# IOX_77_easyEDA_proj_2026-04-07.net
KiCad netlist of a schematic drawn in EasyEDA Pro
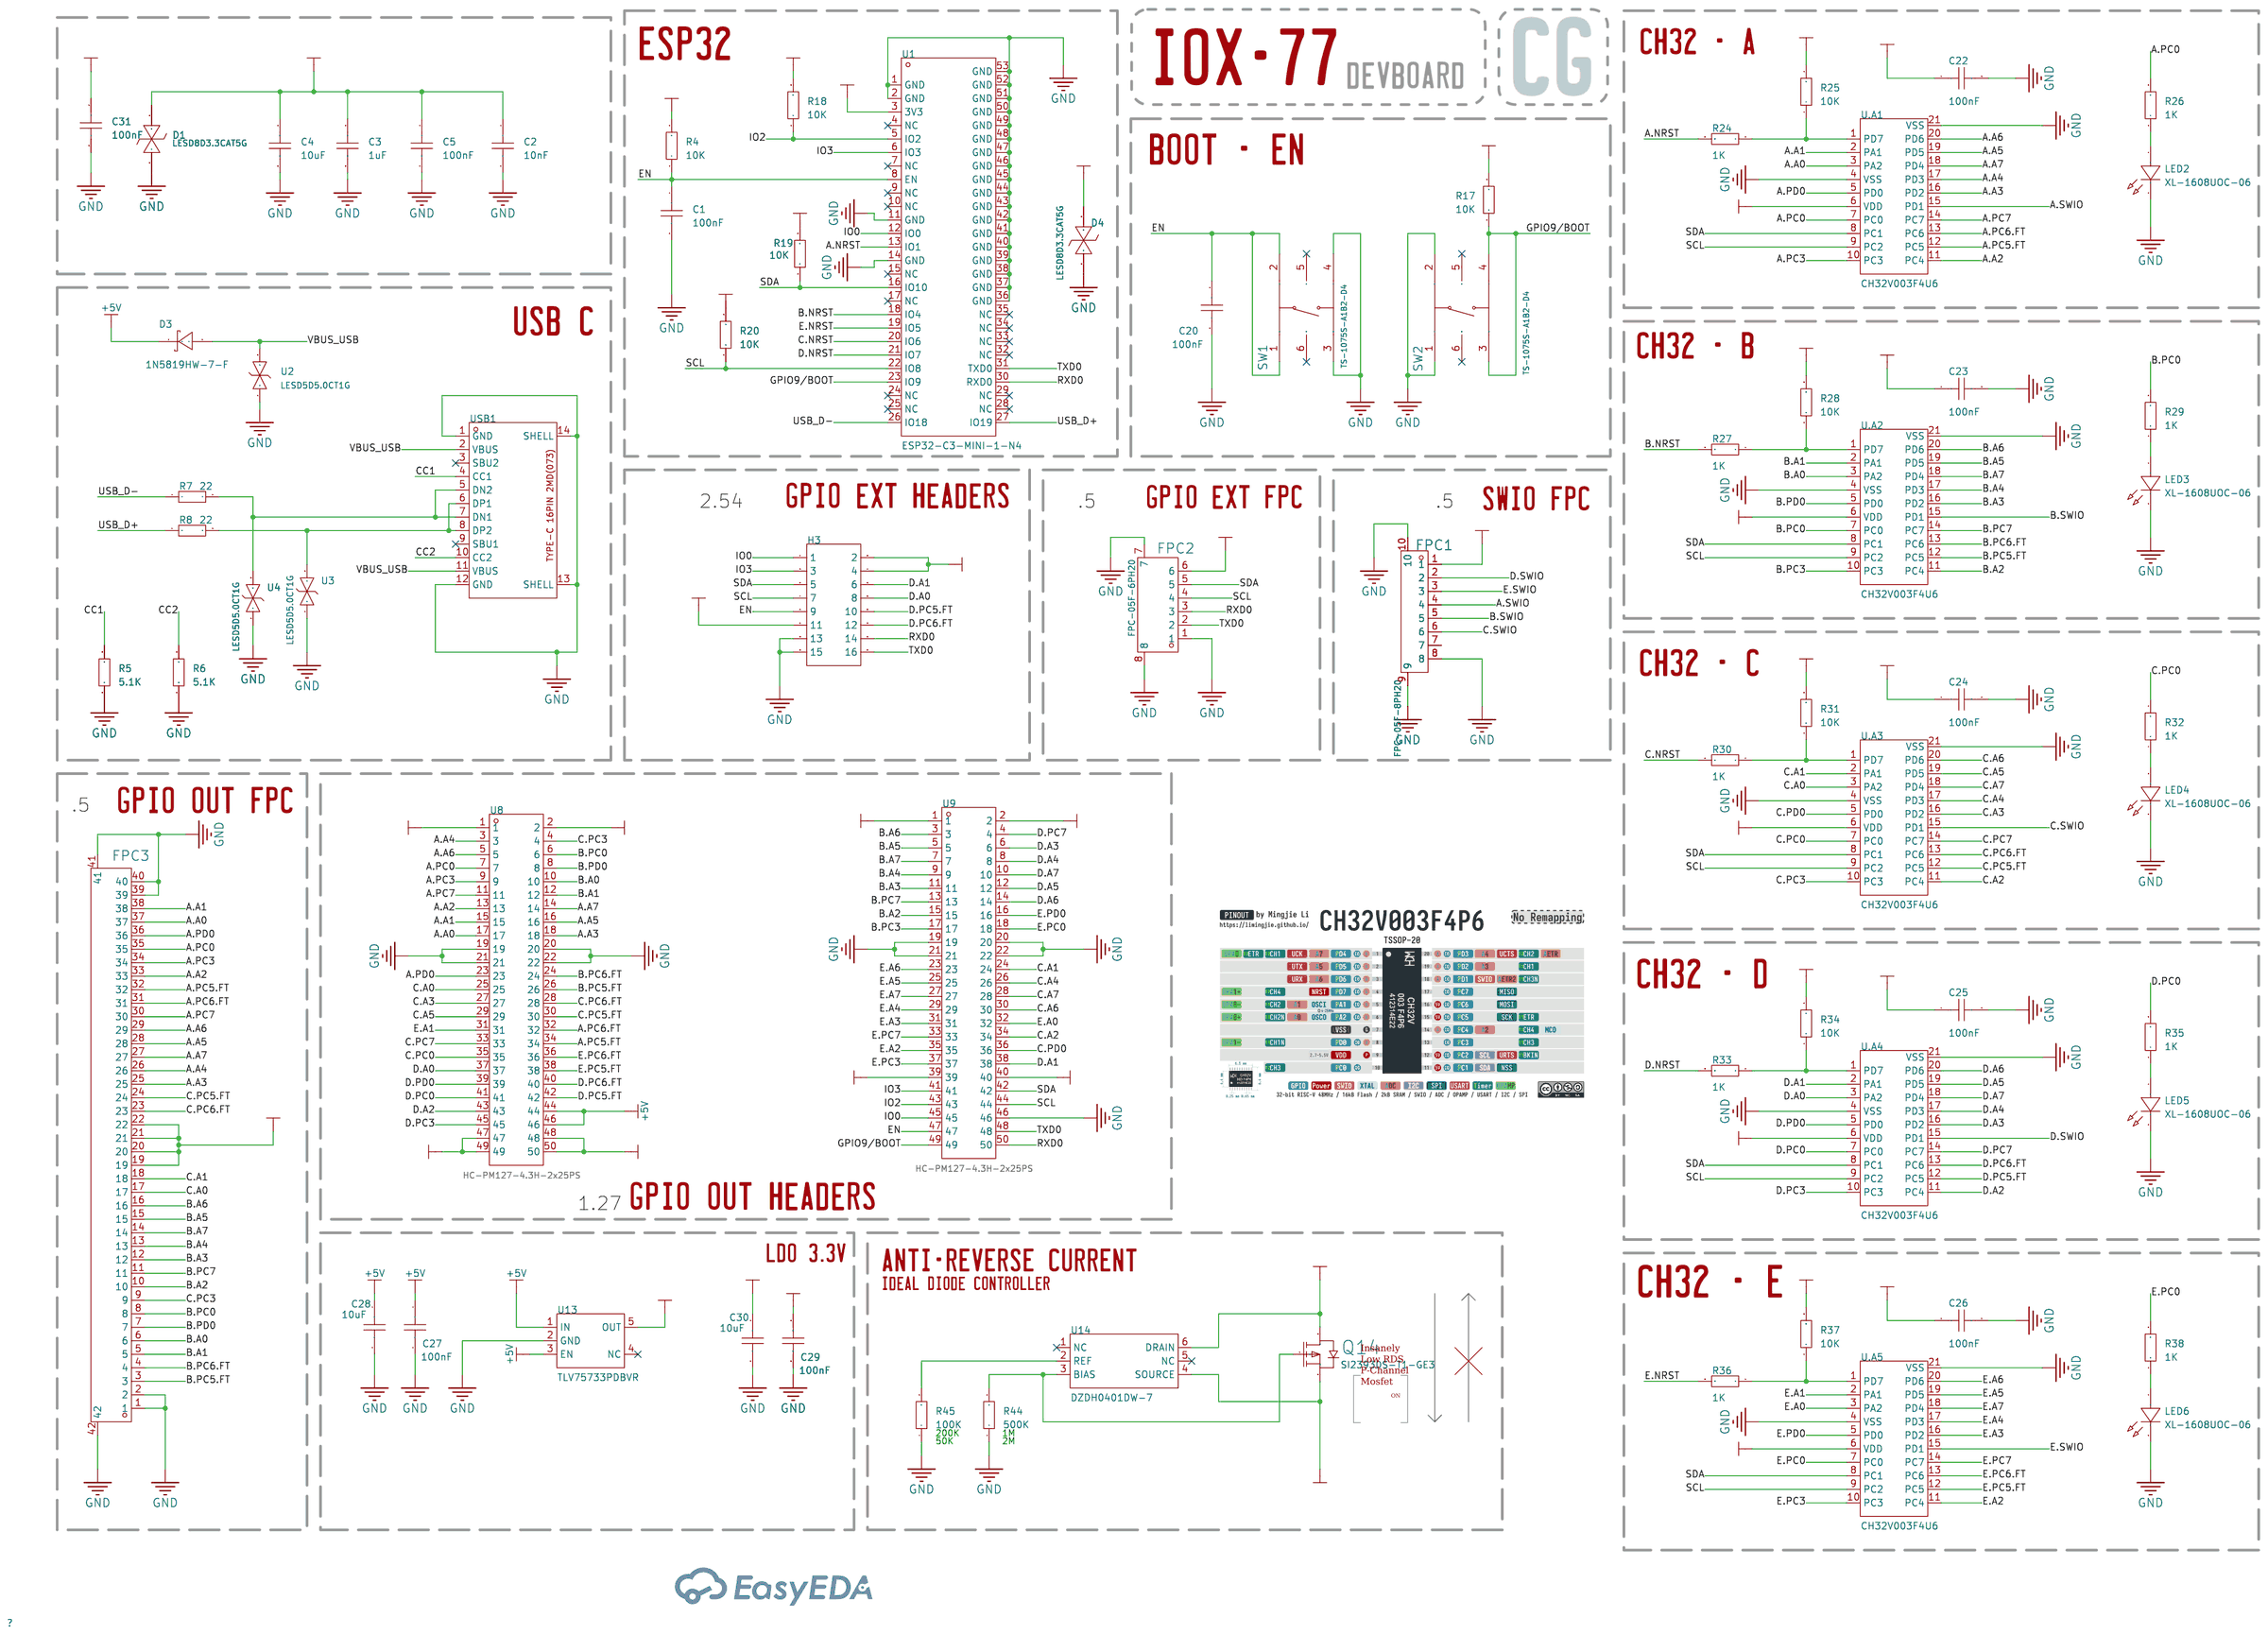
[diagram p0: schematic sheet]

(export (version "E")
  (design (tool "Eeschema 10.0.6"))
  (components
    (comp (ref "C1")
      (value "100nF")
      (footprint "easyedapro:C0603")
      (libsource (lib "easyedapro") (part "CAP"))
    )
    (comp (ref "C2")
      (value "10nF")
      (footprint "easyedapro:C0603")
      (description "Capacitance:10nF Tolerance:±10% Tolerance:±10% Voltage Rating:16V Temperature Coefficient:X7R")
      (fields
        (field (name "Manufacturer Part") "CC0603KRX7R7BB103")
        (field (name "Manufacturer") "YAGEO(国巨)")
      )
      (libsource (lib "easyedapro") (part "CAP"))
    )
    (comp (ref "C3")
      (value "1uF")
      (footprint "easyedapro:C0603")
      (description "Capacitance:1uF Tolerance:±10% Tolerance:±10% Voltage Rating:16V Temperature Coefficient:X5R")
      (fields
        (field (name "Manufacturer Part") "CL10A105KO8NNNC")
        (field (name "Manufacturer") "SAMSUNG(三星)")
      )
      (libsource (lib "easyedapro") (part "CAP"))
    )
    (comp (ref "C4")
      (value "10uF")
      (footprint "easyedapro:C0603")
      (description "Capacitance:10uF Tolerance:±10% Tolerance:±10% Voltage Rating:16V Temperature Coefficient:X5R")
      (fields
        (field (name "Manufacturer Part") "CL21A106KOQNNNE")
        (field (name "Manufacturer") "SAMSUNG(三星)")
      )
      (libsource (lib "easyedapro") (part "CAP"))
    )
    (comp (ref "C5")
      (value "100nF")
      (footprint "easyedapro:C0603")
      (description "Capacitance:100nF Tolerance:±10% Tolerance:±10% Voltage Rating:16V Temperature Coefficient:X7R")
      (fields
        (field (name "Manufacturer Part") "CL10B104KO8NNNC")
        (field (name "Manufacturer") "SAMSUNG(三星)")
      )
      (libsource (lib "easyedapro") (part "CAP"))
    )
    (comp (ref "C20")
      (value "100nF")
      (footprint "easyedapro:C0603")
      (description "Capacitance:100nF Tolerance:±10% Tolerance:±10% Voltage Rating:16V Temperature Coefficient:X7R")
      (fields
        (field (name "Manufacturer Part") "CL10B104KO8NNNC")
        (field (name "Manufacturer") "SAMSUNG(三星)")
      )
      (libsource (lib "easyedapro") (part "CAP"))
    )
    (comp (ref "C22")
      (value "100nF")
      (footprint "easyedapro:C0603")
      (description "Capacitance:100nF Tolerance:±10% Tolerance:±10% Voltage Rating:16V Temperature Coefficient:X7R")
      (fields
        (field (name "Manufacturer Part") "CL10B104KO8NNNC")
        (field (name "Manufacturer") "SAMSUNG(三星)")
      )
      (libsource (lib "easyedapro") (part "CAP"))
    )
    (comp (ref "C23")
      (value "100nF")
      (footprint "easyedapro:C0603")
      (description "Capacitance:100nF Tolerance:±10% Tolerance:±10% Voltage Rating:16V Temperature Coefficient:X7R")
      (fields
        (field (name "Manufacturer Part") "CL10B104KO8NNNC")
        (field (name "Manufacturer") "SAMSUNG(三星)")
      )
      (libsource (lib "easyedapro") (part "CAP"))
    )
    (comp (ref "C24")
      (value "100nF")
      (footprint "easyedapro:C0603")
      (description "Capacitance:100nF Tolerance:±10% Tolerance:±10% Voltage Rating:16V Temperature Coefficient:X7R")
      (fields
        (field (name "Manufacturer Part") "CL10B104KO8NNNC")
        (field (name "Manufacturer") "SAMSUNG(三星)")
      )
      (libsource (lib "easyedapro") (part "CAP"))
    )
    (comp (ref "C25")
      (value "100nF")
      (footprint "easyedapro:C0603")
      (description "Capacitance:100nF Tolerance:±10% Tolerance:±10% Voltage Rating:16V Temperature Coefficient:X7R")
      (fields
        (field (name "Manufacturer Part") "CL10B104KO8NNNC")
        (field (name "Manufacturer") "SAMSUNG(三星)")
      )
      (libsource (lib "easyedapro") (part "CAP"))
    )
    (comp (ref "C26")
      (value "100nF")
      (footprint "easyedapro:C0603")
      (description "Capacitance:100nF Tolerance:±10% Tolerance:±10% Voltage Rating:16V Temperature Coefficient:X7R")
      (fields
        (field (name "Manufacturer Part") "CL10B104KO8NNNC")
        (field (name "Manufacturer") "SAMSUNG(三星)")
      )
      (libsource (lib "easyedapro") (part "CAP"))
    )
    (comp (ref "C27")
      (value "100nF")
      (footprint "easyedapro:C0603")
      (description "Capacitance:100nF Tolerance:±10% Tolerance:±10% Voltage Rating:16V Temperature Coefficient:X7R")
      (fields
        (field (name "Manufacturer Part") "CL10B104KO8NNNC")
        (field (name "Manufacturer") "SAMSUNG(三星)")
      )
      (libsource (lib "easyedapro") (part "CAP"))
    )
    (comp (ref "C28")
      (value "10uF")
      (footprint "easyedapro:C0603")
      (description "Capacitance:10uF Tolerance:±10% Tolerance:±10% Voltage Rating:16V Temperature Coefficient:X5R")
      (fields
        (field (name "Manufacturer Part") "CL21A106KOQNNNE")
        (field (name "Manufacturer") "SAMSUNG(三星)")
      )
      (libsource (lib "easyedapro") (part "CAP"))
    )
    (comp (ref "C29")
      (value "100nF")
      (footprint "easyedapro:C0603")
      (description "Capacitance:100nF Tolerance:±10% Tolerance:±10% Voltage Rating:16V Temperature Coefficient:X7R")
      (fields
        (field (name "Manufacturer Part") "CL10B104KO8NNNC")
        (field (name "Manufacturer") "SAMSUNG(三星)")
      )
      (libsource (lib "easyedapro") (part "CAP"))
    )
    (comp (ref "C30")
      (value "10uF")
      (footprint "easyedapro:C0603")
      (description "Capacitance:10uF Tolerance:±10% Tolerance:±10% Voltage Rating:16V Temperature Coefficient:X5R")
      (fields
        (field (name "Manufacturer Part") "CL21A106KOQNNNE")
        (field (name "Manufacturer") "SAMSUNG(三星)")
      )
      (libsource (lib "easyedapro") (part "CAP"))
    )
    (comp (ref "C31")
      (value "100nF")
      (footprint "easyedapro:C0603")
      (description "Capacitance:10nF Tolerance:±10% Tolerance:±10% Voltage Rating:16V Temperature Coefficient:X7R")
      (fields
        (field (name "Manufacturer Part") "CC0603KRX7R7BB103")
        (field (name "Manufacturer") "YAGEO(国巨)")
      )
      (libsource (lib "easyedapro") (part "CAP"))
    )
    (comp (ref "D1")
      (value "LESD8D3.3CAT5G")
      (footprint "easyedapro:SOD-882_L1.0-W0.6-BI")
      (fields (field (name "Manufacturer") "FUXINSEMI(富芯森美)"))
      (libsource (lib "easyedapro") (part "LESD8D3.3CAT5G_C5563754"))
    )
    (comp (ref "D3")
      (value "1N5819HW-7-F")
      (footprint "easyedapro:SOD-123_L2.7-W1.6-LS3.7-RD")
      (fields (field (name "Manufacturer") "DIODES(美台)"))
      (libsource (lib "easyedapro") (part "1N5819HW-7-F"))
    )
    (comp (ref "D4")
      (value "LESD8D3.3CAT5G")
      (footprint "easyedapro:SOD-882_L1.0-W0.6-BI")
      (fields (field (name "Manufacturer") "FUXINSEMI(富芯森美)"))
      (libsource (lib "easyedapro") (part "LESD8D3.3CAT5G_C5563754"))
    )
    (comp (ref "FPC1")
      (value "FPC-05F-8PH20")
      (footprint "easyedapro:FPC-SMD_8P-P0.50_FPC-05F-8PH20")
      (fields (field (name "Manufacturer") "XUNPU(讯普)"))
      (libsource (lib "easyedapro") (part "FPC-05F-8PH20"))
    )
    (comp (ref "FPC2")
      (value "FPC-05F-6PH20")
      (footprint "easyedapro:FPC-SMD_6P-P0.50_XUNPU_FPC-05F-6PH20")
      (fields (field (name "Manufacturer") "XUNPU(讯普)"))
      (libsource (lib "easyedapro") (part "FPC-05F-6PH20"))
    )
    (comp (ref "FPC3")
      (value "FPC-05F-40PH20")
      (footprint "easyedapro:FPC-SMD_40P-P0.50_FPC-05F-40PH20")
      (fields (field (name "Manufacturer") "XUNPU(讯普)"))
      (libsource (lib "easyedapro") (part "FPC-05F-40PH20"))
    )
    (comp (ref "H3")
      (value "~")
      (footprint "easyedapro:HDR-TH_16P-P2.54-V-M-R2-C8-S2.54")
      (libsource (lib "easyedapro") (part "HDR-M-2.54_2x8"))
    )
    (comp (ref "LED2")
      (value "XL-1608UOC-06")
      (footprint "easyedapro:LED0603-R-RD_ORANGE")
      (fields (field (name "Manufacturer") "XINGLIGHT(成兴光)"))
      (libsource (lib "easyedapro") (part "XL-1608UOC-06"))
    )
    (comp (ref "LED3")
      (value "XL-1608UOC-06")
      (footprint "easyedapro:LED0603-R-RD_ORANGE")
      (fields (field (name "Manufacturer") "XINGLIGHT(成兴光)"))
      (libsource (lib "easyedapro") (part "XL-1608UOC-06"))
    )
    (comp (ref "LED4")
      (value "XL-1608UOC-06")
      (footprint "easyedapro:LED0603-R-RD_ORANGE")
      (fields (field (name "Manufacturer") "XINGLIGHT(成兴光)"))
      (libsource (lib "easyedapro") (part "XL-1608UOC-06"))
    )
    (comp (ref "LED5")
      (value "XL-1608UOC-06")
      (footprint "easyedapro:LED0603-R-RD_ORANGE")
      (fields (field (name "Manufacturer") "XINGLIGHT(成兴光)"))
      (libsource (lib "easyedapro") (part "XL-1608UOC-06"))
    )
    (comp (ref "LED6")
      (value "XL-1608UOC-06")
      (footprint "easyedapro:LED0603-R-RD_ORANGE")
      (fields (field (name "Manufacturer") "XINGLIGHT(成兴光)"))
      (libsource (lib "easyedapro") (part "XL-1608UOC-06"))
    )
    (comp (ref "Q14")
      (value "SI2393DS-T1-GE3")
      (footprint "easyedapro:SOT-23-3_L2.9-W1.3-P1.90-LS2.4-BR")
      (fields (field (name "Manufacturer") "VISHAY(威世)"))
      (libsource (lib "easyedapro") (part "SI2393DS-T1-GE3"))
    )
    (comp (ref "R4") (value "10K") (footprint "easyedapro:R0603") (libsource (lib "easyedapro") (part "Res")))
    (comp (ref "R5")
      (value "5.1K")
      (footprint "easyedapro:R0603")
      (libsource (lib "easyedapro") (part "Res"))
    )
    (comp (ref "R6")
      (value "5.1K")
      (footprint "easyedapro:R0603")
      (libsource (lib "easyedapro") (part "Res"))
    )
    (comp (ref "R7") (value "22") (footprint "easyedapro:R0603") (libsource (lib "easyedapro") (part "Res")))
    (comp (ref "R8") (value "22") (footprint "easyedapro:R0603") (libsource (lib "easyedapro") (part "Res")))
    (comp (ref "R17")
      (value "10K")
      (footprint "easyedapro:R0603")
      (libsource (lib "easyedapro") (part "Res"))
    )
    (comp (ref "R18")
      (value "10K")
      (footprint "easyedapro:R0603")
      (libsource (lib "easyedapro") (part "Res"))
    )
    (comp (ref "R19")
      (value "10K")
      (footprint "easyedapro:R0603")
      (libsource (lib "easyedapro") (part "Res"))
    )
    (comp (ref "R20")
      (value "10K")
      (footprint "easyedapro:R0603")
      (libsource (lib "easyedapro") (part "Res"))
    )
    (comp (ref "R24") (value "1K") (footprint "easyedapro:R0603") (libsource (lib "easyedapro") (part "Res")))
    (comp (ref "R25")
      (value "10K")
      (footprint "easyedapro:R0603")
      (libsource (lib "easyedapro") (part "Res"))
    )
    (comp (ref "R26") (value "1K") (footprint "easyedapro:R0603") (libsource (lib "easyedapro") (part "Res")))
    (comp (ref "R27") (value "1K") (footprint "easyedapro:R0603") (libsource (lib "easyedapro") (part "Res")))
    (comp (ref "R28")
      (value "10K")
      (footprint "easyedapro:R0603")
      (libsource (lib "easyedapro") (part "Res"))
    )
    (comp (ref "R29") (value "1K") (footprint "easyedapro:R0603") (libsource (lib "easyedapro") (part "Res")))
    (comp (ref "R30") (value "1K") (footprint "easyedapro:R0603") (libsource (lib "easyedapro") (part "Res")))
    (comp (ref "R31")
      (value "10K")
      (footprint "easyedapro:R0603")
      (libsource (lib "easyedapro") (part "Res"))
    )
    (comp (ref "R32") (value "1K") (footprint "easyedapro:R0603") (libsource (lib "easyedapro") (part "Res")))
    (comp (ref "R33") (value "1K") (footprint "easyedapro:R0603") (libsource (lib "easyedapro") (part "Res")))
    (comp (ref "R34")
      (value "10K")
      (footprint "easyedapro:R0603")
      (libsource (lib "easyedapro") (part "Res"))
    )
    (comp (ref "R35") (value "1K") (footprint "easyedapro:R0603") (libsource (lib "easyedapro") (part "Res")))
    (comp (ref "R36") (value "1K") (footprint "easyedapro:R0603") (libsource (lib "easyedapro") (part "Res")))
    (comp (ref "R37")
      (value "10K")
      (footprint "easyedapro:R0603")
      (libsource (lib "easyedapro") (part "Res"))
    )
    (comp (ref "R38") (value "1K") (footprint "easyedapro:R0603") (libsource (lib "easyedapro") (part "Res")))
    (comp (ref "R44")
      (value "500K")
      (footprint "easyedapro:R0603")
      (libsource (lib "easyedapro") (part "Res"))
    )
    (comp (ref "R45")
      (value "100K")
      (footprint "easyedapro:R0603")
      (libsource (lib "easyedapro") (part "Res"))
    )
    (comp (ref "SW1")
      (value "TS-1075S-A1B2-D4")
      (footprint "easyedapro:SW-SMD_4P-L3.1-W3.1-P2.20-LS4.0")
      (fields (field (name "Manufacturer") "Yuandi(元迪)"))
      (libsource (lib "easyedapro") (part "TS-1075S-A1B2-D4"))
    )
    (comp (ref "SW2")
      (value "TS-1075S-A1B2-D4")
      (footprint "easyedapro:SW-SMD_4P-L3.1-W3.1-P2.20-LS4.0")
      (fields (field (name "Manufacturer") "Yuandi(元迪)"))
      (libsource (lib "easyedapro") (part "TS-1075S-A1B2-D4"))
    )
    (comp (ref "U.A1")
      (value "CH32V003F4U6")
      (footprint "easyedapro:QFN-20_L3.0-W3.0-P0.40-TL-EP1.7")
      (description "CPU Core:RISC-V CPU Maximum Speed:48MHz Program Storage Size:16KB Number of I/O:18 Applications:-")
      (fields (field (name "Manufacturer") "WCH(南京沁恒)"))
      (libsource (lib "easyedapro") (part "CH32V003F4U6"))
    )
    (comp (ref "U.A2")
      (value "CH32V003F4U6")
      (footprint "easyedapro:QFN-20_L3.0-W3.0-P0.40-TL-EP1.7")
      (description "CPU Core:RISC-V CPU Maximum Speed:48MHz Program Storage Size:16KB Number of I/O:18 Applications:-")
      (fields (field (name "Manufacturer") "WCH(南京沁恒)"))
      (libsource (lib "easyedapro") (part "CH32V003F4U6"))
    )
    (comp (ref "U.A3")
      (value "CH32V003F4U6")
      (footprint "easyedapro:QFN-20_L3.0-W3.0-P0.40-TL-EP1.7")
      (description "CPU Core:RISC-V CPU Maximum Speed:48MHz Program Storage Size:16KB Number of I/O:18 Applications:-")
      (fields (field (name "Manufacturer") "WCH(南京沁恒)"))
      (libsource (lib "easyedapro") (part "CH32V003F4U6"))
    )
    (comp (ref "U.A4")
      (value "CH32V003F4U6")
      (footprint "easyedapro:QFN-20_L3.0-W3.0-P0.40-TL-EP1.7")
      (description "CPU Core:RISC-V CPU Maximum Speed:48MHz Program Storage Size:16KB Number of I/O:18 Applications:-")
      (fields (field (name "Manufacturer") "WCH(南京沁恒)"))
      (libsource (lib "easyedapro") (part "CH32V003F4U6"))
    )
    (comp (ref "U.A5")
      (value "CH32V003F4U6")
      (footprint "easyedapro:QFN-20_L3.0-W3.0-P0.40-TL-EP1.7")
      (description "CPU Core:RISC-V CPU Maximum Speed:48MHz Program Storage Size:16KB Number of I/O:18 Applications:-")
      (fields (field (name "Manufacturer") "WCH(南京沁恒)"))
      (libsource (lib "easyedapro") (part "CH32V003F4U6"))
    )
    (comp (ref "U1")
      (value "ESP32-C3-MINI-1-N4")
      (footprint "easyedapro:WIFIM-SMD_ESP32-C3-MINI-1")
      (fields (field (name "Manufacturer") "ESPRESSIF(乐鑫)"))
      (libsource (lib "easyedapro") (part "ESP32-C3-MINI-1-N4"))
    )
    (comp (ref "U2")
      (value "LESD5D5.0CT1G")
      (footprint "easyedapro:SOD-523_L1.2-W0.8-LS1.6-BI")
      (fields (field (name "Manufacturer") "KUU"))
      (libsource (lib "easyedapro") (part "LESD5D5.0CT1G_C7433850"))
    )
    (comp (ref "U3")
      (value "LESD5D5.0CT1G")
      (footprint "easyedapro:SOD-523_L1.2-W0.8-LS1.6-BI")
      (fields (field (name "Manufacturer") "KUU"))
      (libsource (lib "easyedapro") (part "LESD5D5.0CT1G_C7433850"))
    )
    (comp (ref "U4")
      (value "LESD5D5.0CT1G")
      (footprint "easyedapro:SOD-523_L1.2-W0.8-LS1.6-BI")
      (fields (field (name "Manufacturer") "KUU"))
      (libsource (lib "easyedapro") (part "LESD5D5.0CT1G_C7433850"))
    )
    (comp (ref "U8")
      (value "HC-PM127-4.3H-2x25PS")
      (footprint "easyedapro:HDR-SMD_50P-P1.27-V-F-R2-C25-LS4.8")
      (fields (field (name "Manufacturer") "HC(虹成电子)"))
      (libsource (lib "easyedapro") (part "HC-PM127-4.3H-2X25PS"))
    )
    (comp (ref "U9")
      (value "HC-PM127-4.3H-2x25PS")
      (footprint "easyedapro:HDR-SMD_50P-P1.27-V-F-R2-C25-LS4.8")
      (fields (field (name "Manufacturer") "HC(虹成电子)"))
      (libsource (lib "easyedapro") (part "HC-PM127-4.3H-2X25PS"))
    )
    (comp (ref "U13")
      (value "TLV75733PDBVR")
      (footprint "easyedapro:SOT-23-5_L2.9-W1.6-P0.95-LS2.8-BL")
      (fields (field (name "Manufacturer") "TI(德州仪器)"))
      (libsource (lib "easyedapro") (part "TLV75733PDBVR"))
    )
    (comp (ref "U14")
      (value "DZDH0401DW-7")
      (footprint "easyedapro:SOT-363_L2.0-W1.3-P0.65-LS2.1-BR")
      (fields (field (name "Manufacturer") "DIODES(美台)"))
      (libsource (lib "easyedapro") (part "DZDH0401DW-7"))
    )
    (comp (ref "USB1")
      (value "TYPE-C 16PIN 2MD(073)")
      (footprint "easyedapro:USB-C-SMD_TYPE-C-6PIN-2MD-073")
      (fields (field (name "Manufacturer") "SHOU HAN(首韩)"))
      (libsource (lib "easyedapro") (part "TYPE-C 16PIN 2MD(073)"))
    )
  )
  (nets
    (net (code "1") (name "+3.3V") (class "Default")
      (node (ref "C2") (pin "1") (pinfunction "1_1") (pintype "input"))
      (node (ref "C22") (pin "1") (pinfunction "1_1") (pintype "input"))
      (node (ref "C23") (pin "1") (pinfunction "1_1") (pintype "input"))
      (node (ref "C24") (pin "1") (pinfunction "1_1") (pintype "input"))
      (node (ref "C25") (pin "1") (pinfunction "1_1") (pintype "input"))
      (node (ref "C26") (pin "1") (pinfunction "1_1") (pintype "input"))
      (node (ref "C3") (pin "1") (pinfunction "1_1") (pintype "input"))
      (node (ref "C31") (pin "1") (pinfunction "1_1") (pintype "input"))
      (node (ref "C4") (pin "1") (pinfunction "1_1") (pintype "input"))
      (node (ref "C5") (pin "1") (pinfunction "1_1") (pintype "input"))
      (node (ref "D1") (pin "2") (pinfunction "2_2") (pintype "unspecified"))
      (node (ref "D4") (pin "2") (pinfunction "2_2") (pintype "unspecified"))
      (node (ref "FPC1") (pin "1") (pinfunction "1_1") (pintype "unspecified"))
      (node (ref "FPC2") (pin "6") (pinfunction "6_6") (pintype "input"))
      (node (ref "FPC3") (pin "19") (pinfunction "19_19") (pintype "input"))
      (node (ref "FPC3") (pin "20") (pinfunction "20_20") (pintype "input"))
      (node (ref "FPC3") (pin "21") (pinfunction "21_21") (pintype "input"))
      (node (ref "FPC3") (pin "22") (pinfunction "22_22") (pintype "input"))
      (node (ref "H3") (pin "2") (pinfunction "2_2") (pintype "input"))
      (node (ref "H3") (pin "4") (pinfunction "4_4") (pintype "input"))
      (node (ref "Q14") (pin "2") (pinfunction "S_2") (pintype "unspecified"))
      (node (ref "R17") (pin "2") (pinfunction "2_2") (pintype "input"))
      (node (ref "R18") (pin "2") (pinfunction "2_2") (pintype "input"))
      (node (ref "R19") (pin "2") (pinfunction "2_2") (pintype "input"))
      (node (ref "R20") (pin "2") (pinfunction "2_2") (pintype "input"))
      (node (ref "R25") (pin "2") (pinfunction "2_2") (pintype "input"))
      (node (ref "R28") (pin "2") (pinfunction "2_2") (pintype "input"))
      (node (ref "R31") (pin "2") (pinfunction "2_2") (pintype "input"))
      (node (ref "R34") (pin "2") (pinfunction "2_2") (pintype "input"))
      (node (ref "R37") (pin "2") (pinfunction "2_2") (pintype "input"))
      (node (ref "R4") (pin "2") (pinfunction "2_2") (pintype "input"))
      (node (ref "U.A1") (pin "6") (pinfunction "VDD_6") (pintype "unspecified"))
      (node (ref "U.A2") (pin "6") (pinfunction "VDD_6") (pintype "unspecified"))
      (node (ref "U.A3") (pin "6") (pinfunction "VDD_6") (pintype "unspecified"))
      (node (ref "U.A4") (pin "6") (pinfunction "VDD_6") (pintype "unspecified"))
      (node (ref "U.A5") (pin "6") (pinfunction "VDD_6") (pintype "unspecified"))
      (node (ref "U1") (pin "3") (pinfunction "3V3_3") (pintype "unspecified"))
      (node (ref "U14") (pin "4") (pinfunction "SOURCE_4") (pintype "unspecified"))
      (node (ref "U8") (pin "1") (pinfunction "1_1") (pintype "unspecified"))
      (node (ref "U8") (pin "2") (pinfunction "2_2") (pintype "unspecified"))
      (node (ref "U8") (pin "47") (pinfunction "47_47") (pintype "unspecified"))
      (node (ref "U8") (pin "48") (pinfunction "48_48") (pintype "unspecified"))
      (node (ref "U8") (pin "49") (pinfunction "49_49") (pintype "unspecified"))
      (node (ref "U8") (pin "50") (pinfunction "50_50") (pintype "unspecified"))
      (node (ref "U9") (pin "1") (pinfunction "1_1") (pintype "unspecified"))
      (node (ref "U9") (pin "2") (pinfunction "2_2") (pintype "unspecified"))
      (node (ref "U9") (pin "39") (pinfunction "39_39") (pintype "unspecified"))
      (node (ref "U9") (pin "40") (pinfunction "40_40") (pintype "unspecified"))
    )
    (net (code "2") (name "+3.3V.LDO") (class "Default")
      (node (ref "C29") (pin "1") (pinfunction "1_1") (pintype "input"))
      (node (ref "C30") (pin "1") (pinfunction "1_1") (pintype "input"))
      (node (ref "Q14") (pin "3") (pinfunction "D_3") (pintype "unspecified"))
      (node (ref "U13") (pin "5") (pinfunction "OUT_5") (pintype "unspecified"))
      (node (ref "U14") (pin "6") (pinfunction "DRAIN_6") (pintype "unspecified"))
    )
    (net (code "3") (name "+5V") (class "Default")
      (node (ref "C27") (pin "1") (pinfunction "1_1") (pintype "input"))
      (node (ref "C28") (pin "1") (pinfunction "1_1") (pintype "input"))
      (node (ref "D3") (pin "1") (pinfunction "K_1") (pintype "unspecified"))
      (node (ref "H3") (pin "11") (pinfunction "11_11") (pintype "input"))
      (node (ref "U13") (pin "1") (pinfunction "IN_1") (pintype "unspecified"))
      (node (ref "U13") (pin "3") (pinfunction "EN_3") (pintype "unspecified"))
      (node (ref "U8") (pin "44") (pinfunction "44_44") (pintype "unspecified"))
      (node (ref "U8") (pin "46") (pinfunction "46_46") (pintype "unspecified"))
    )
    (net (code "4") (name "/A.A0") (class "Default")
      (node (ref "FPC3") (pin "37") (pinfunction "37_37") (pintype "input"))
      (node (ref "U.A1") (pin "3") (pinfunction "PA2_3") (pintype "unspecified"))
      (node (ref "U8") (pin "17") (pinfunction "17_17") (pintype "unspecified"))
    )
    (net (code "5") (name "/A.A1") (class "Default")
      (node (ref "FPC3") (pin "38") (pinfunction "38_38") (pintype "input"))
      (node (ref "U.A1") (pin "2") (pinfunction "PA1_2") (pintype "unspecified"))
      (node (ref "U8") (pin "15") (pinfunction "15_15") (pintype "unspecified"))
    )
    (net (code "6") (name "/A.A2") (class "Default")
      (node (ref "FPC3") (pin "33") (pinfunction "33_33") (pintype "input"))
      (node (ref "U.A1") (pin "11") (pinfunction "PC4_11") (pintype "unspecified"))
      (node (ref "U8") (pin "13") (pinfunction "13_13") (pintype "unspecified"))
    )
    (net (code "7") (name "/A.A3") (class "Default")
      (node (ref "FPC3") (pin "25") (pinfunction "25_25") (pintype "input"))
      (node (ref "U.A1") (pin "16") (pinfunction "PD2_16") (pintype "unspecified"))
      (node (ref "U8") (pin "18") (pinfunction "18_18") (pintype "unspecified"))
    )
    (net (code "8") (name "/A.A4") (class "Default")
      (node (ref "FPC3") (pin "26") (pinfunction "26_26") (pintype "input"))
      (node (ref "U.A1") (pin "17") (pinfunction "PD3_17") (pintype "unspecified"))
      (node (ref "U8") (pin "3") (pinfunction "3_3") (pintype "unspecified"))
    )
    (net (code "9") (name "/A.A5") (class "Default")
      (node (ref "FPC3") (pin "28") (pinfunction "28_28") (pintype "input"))
      (node (ref "U.A1") (pin "19") (pinfunction "PD5_19") (pintype "unspecified"))
      (node (ref "U8") (pin "16") (pinfunction "16_16") (pintype "unspecified"))
    )
    (net (code "10") (name "/A.A6") (class "Default")
      (node (ref "FPC3") (pin "29") (pinfunction "29_29") (pintype "input"))
      (node (ref "U.A1") (pin "20") (pinfunction "PD6_20") (pintype "unspecified"))
      (node (ref "U8") (pin "5") (pinfunction "5_5") (pintype "unspecified"))
    )
    (net (code "11") (name "/A.A7") (class "Default")
      (node (ref "FPC3") (pin "27") (pinfunction "27_27") (pintype "input"))
      (node (ref "U.A1") (pin "18") (pinfunction "PD4_18") (pintype "unspecified"))
      (node (ref "U8") (pin "14") (pinfunction "14_14") (pintype "unspecified"))
    )
    (net (code "12") (name "/A.NRST") (class "Default")
      (node (ref "R24") (pin "2") (pinfunction "2_2") (pintype "input"))
      (node (ref "U1") (pin "13") (pinfunction "IO1_13") (pintype "unspecified"))
    )
    (net (code "13") (name "/A.PC0") (class "Default")
      (node (ref "FPC3") (pin "35") (pinfunction "35_35") (pintype "input"))
      (node (ref "R26") (pin "2") (pinfunction "2_2") (pintype "input"))
      (node (ref "U.A1") (pin "7") (pinfunction "PC0_7") (pintype "unspecified"))
      (node (ref "U8") (pin "7") (pinfunction "7_7") (pintype "unspecified"))
    )
    (net (code "14") (name "/A.PC3") (class "Default")
      (node (ref "FPC3") (pin "34") (pinfunction "34_34") (pintype "input"))
      (node (ref "U.A1") (pin "10") (pinfunction "PC3_10") (pintype "unspecified"))
      (node (ref "U8") (pin "9") (pinfunction "9_9") (pintype "unspecified"))
    )
    (net (code "15") (name "/A.PC5.FT") (class "Default")
      (node (ref "FPC3") (pin "32") (pinfunction "32_32") (pintype "input"))
      (node (ref "U.A1") (pin "12") (pinfunction "PC5_12") (pintype "unspecified"))
      (node (ref "U8") (pin "34") (pinfunction "34_34") (pintype "unspecified"))
    )
    (net (code "16") (name "/A.PC6.FT") (class "Default")
      (node (ref "FPC3") (pin "31") (pinfunction "31_31") (pintype "input"))
      (node (ref "U.A1") (pin "13") (pinfunction "PC6_13") (pintype "unspecified"))
      (node (ref "U8") (pin "32") (pinfunction "32_32") (pintype "unspecified"))
    )
    (net (code "17") (name "/A.PC7") (class "Default")
      (node (ref "FPC3") (pin "30") (pinfunction "30_30") (pintype "input"))
      (node (ref "U.A1") (pin "14") (pinfunction "PC7_14") (pintype "unspecified"))
      (node (ref "U8") (pin "11") (pinfunction "11_11") (pintype "unspecified"))
    )
    (net (code "18") (name "/A.PD0") (class "Default")
      (node (ref "FPC3") (pin "36") (pinfunction "36_36") (pintype "input"))
      (node (ref "U.A1") (pin "5") (pinfunction "PD0_5") (pintype "unspecified"))
      (node (ref "U8") (pin "23") (pinfunction "23_23") (pintype "unspecified"))
    )
    (net (code "19") (name "/A.SWIO") (class "Default")
      (node (ref "FPC1") (pin "4") (pinfunction "4_4") (pintype "unspecified"))
      (node (ref "U.A1") (pin "15") (pinfunction "PD1_15") (pintype "unspecified"))
    )
    (net (code "20") (name "/B.A0") (class "Default")
      (node (ref "FPC3") (pin "6") (pinfunction "6_6") (pintype "input"))
      (node (ref "U.A2") (pin "3") (pinfunction "PA2_3") (pintype "unspecified"))
      (node (ref "U8") (pin "10") (pinfunction "10_10") (pintype "unspecified"))
    )
    (net (code "21") (name "/B.A1") (class "Default")
      (node (ref "FPC3") (pin "5") (pinfunction "5_5") (pintype "input"))
      (node (ref "U.A2") (pin "2") (pinfunction "PA1_2") (pintype "unspecified"))
      (node (ref "U8") (pin "12") (pinfunction "12_12") (pintype "unspecified"))
    )
    (net (code "22") (name "/B.A2") (class "Default")
      (node (ref "FPC3") (pin "10") (pinfunction "10_10") (pintype "input"))
      (node (ref "U.A2") (pin "11") (pinfunction "PC4_11") (pintype "unspecified"))
      (node (ref "U9") (pin "15") (pinfunction "15_15") (pintype "unspecified"))
    )
    (net (code "23") (name "/B.A3") (class "Default")
      (node (ref "FPC3") (pin "12") (pinfunction "12_12") (pintype "input"))
      (node (ref "U.A2") (pin "16") (pinfunction "PD2_16") (pintype "unspecified"))
      (node (ref "U9") (pin "11") (pinfunction "11_11") (pintype "unspecified"))
    )
    (net (code "24") (name "/B.A4") (class "Default")
      (node (ref "FPC3") (pin "13") (pinfunction "13_13") (pintype "input"))
      (node (ref "U.A2") (pin "17") (pinfunction "PD3_17") (pintype "unspecified"))
      (node (ref "U9") (pin "9") (pinfunction "9_9") (pintype "unspecified"))
    )
    (net (code "25") (name "/B.A5") (class "Default")
      (node (ref "FPC3") (pin "15") (pinfunction "15_15") (pintype "input"))
      (node (ref "U.A2") (pin "19") (pinfunction "PD5_19") (pintype "unspecified"))
      (node (ref "U9") (pin "5") (pinfunction "5_5") (pintype "unspecified"))
    )
    (net (code "26") (name "/B.A6") (class "Default")
      (node (ref "FPC3") (pin "16") (pinfunction "16_16") (pintype "input"))
      (node (ref "U.A2") (pin "20") (pinfunction "PD6_20") (pintype "unspecified"))
      (node (ref "U9") (pin "3") (pinfunction "3_3") (pintype "unspecified"))
    )
    (net (code "27") (name "/B.A7") (class "Default")
      (node (ref "FPC3") (pin "14") (pinfunction "14_14") (pintype "input"))
      (node (ref "U.A2") (pin "18") (pinfunction "PD4_18") (pintype "unspecified"))
      (node (ref "U9") (pin "7") (pinfunction "7_7") (pintype "unspecified"))
    )
    (net (code "28") (name "/B.NRST") (class "Default")
      (node (ref "R27") (pin "2") (pinfunction "2_2") (pintype "input"))
      (node (ref "U1") (pin "18") (pinfunction "IO4_18") (pintype "unspecified"))
    )
    (net (code "29") (name "/B.PC0") (class "Default")
      (node (ref "FPC3") (pin "8") (pinfunction "8_8") (pintype "input"))
      (node (ref "R29") (pin "2") (pinfunction "2_2") (pintype "input"))
      (node (ref "U.A2") (pin "7") (pinfunction "PC0_7") (pintype "unspecified"))
      (node (ref "U8") (pin "6") (pinfunction "6_6") (pintype "unspecified"))
    )
    (net (code "30") (name "/B.PC3") (class "Default")
      (node (ref "U.A2") (pin "10") (pinfunction "PC3_10") (pintype "unspecified"))
      (node (ref "U9") (pin "17") (pinfunction "17_17") (pintype "unspecified"))
    )
    (net (code "31") (name "/B.PC5.FT") (class "Default")
      (node (ref "FPC3") (pin "3") (pinfunction "3_3") (pintype "input"))
      (node (ref "U.A2") (pin "12") (pinfunction "PC5_12") (pintype "unspecified"))
      (node (ref "U8") (pin "26") (pinfunction "26_26") (pintype "unspecified"))
    )
    (net (code "32") (name "/B.PC6.FT") (class "Default")
      (node (ref "FPC3") (pin "4") (pinfunction "4_4") (pintype "input"))
      (node (ref "U.A2") (pin "13") (pinfunction "PC6_13") (pintype "unspecified"))
      (node (ref "U8") (pin "24") (pinfunction "24_24") (pintype "unspecified"))
    )
    (net (code "33") (name "/B.PC7") (class "Default")
      (node (ref "FPC3") (pin "11") (pinfunction "11_11") (pintype "input"))
      (node (ref "U.A2") (pin "14") (pinfunction "PC7_14") (pintype "unspecified"))
      (node (ref "U9") (pin "13") (pinfunction "13_13") (pintype "unspecified"))
    )
    (net (code "34") (name "/B.PD0") (class "Default")
      (node (ref "FPC3") (pin "7") (pinfunction "7_7") (pintype "input"))
      (node (ref "U.A2") (pin "5") (pinfunction "PD0_5") (pintype "unspecified"))
      (node (ref "U8") (pin "8") (pinfunction "8_8") (pintype "unspecified"))
    )
    (net (code "35") (name "/B.SWIO") (class "Default")
      (node (ref "FPC1") (pin "5") (pinfunction "5_5") (pintype "unspecified"))
      (node (ref "U.A2") (pin "15") (pinfunction "PD1_15") (pintype "unspecified"))
    )
    (net (code "36") (name "/C.A0") (class "Default")
      (node (ref "FPC3") (pin "17") (pinfunction "17_17") (pintype "input"))
      (node (ref "U.A3") (pin "3") (pinfunction "PA2_3") (pintype "unspecified"))
      (node (ref "U8") (pin "25") (pinfunction "25_25") (pintype "unspecified"))
    )
    (net (code "37") (name "/C.A1") (class "Default")
      (node (ref "FPC3") (pin "18") (pinfunction "18_18") (pintype "input"))
      (node (ref "U.A3") (pin "2") (pinfunction "PA1_2") (pintype "unspecified"))
      (node (ref "U9") (pin "24") (pinfunction "24_24") (pintype "unspecified"))
    )
    (net (code "38") (name "/C.A2") (class "Default")
      (node (ref "U.A3") (pin "11") (pinfunction "PC4_11") (pintype "unspecified"))
      (node (ref "U9") (pin "34") (pinfunction "34_34") (pintype "unspecified"))
    )
    (net (code "39") (name "/C.A3") (class "Default")
      (node (ref "U.A3") (pin "16") (pinfunction "PD2_16") (pintype "unspecified"))
      (node (ref "U8") (pin "27") (pinfunction "27_27") (pintype "unspecified"))
    )
    (net (code "40") (name "/C.A4") (class "Default")
      (node (ref "U.A3") (pin "17") (pinfunction "PD3_17") (pintype "unspecified"))
      (node (ref "U9") (pin "26") (pinfunction "26_26") (pintype "unspecified"))
    )
    (net (code "41") (name "/C.A5") (class "Default")
      (node (ref "U.A3") (pin "19") (pinfunction "PD5_19") (pintype "unspecified"))
      (node (ref "U8") (pin "29") (pinfunction "29_29") (pintype "unspecified"))
    )
    (net (code "42") (name "/C.A6") (class "Default")
      (node (ref "U.A3") (pin "20") (pinfunction "PD6_20") (pintype "unspecified"))
      (node (ref "U9") (pin "30") (pinfunction "30_30") (pintype "unspecified"))
    )
    (net (code "43") (name "/C.A7") (class "Default")
      (node (ref "U.A3") (pin "18") (pinfunction "PD4_18") (pintype "unspecified"))
      (node (ref "U9") (pin "28") (pinfunction "28_28") (pintype "unspecified"))
    )
    (net (code "44") (name "/C.NRST") (class "Default")
      (node (ref "R30") (pin "2") (pinfunction "2_2") (pintype "input"))
      (node (ref "U1") (pin "20") (pinfunction "IO6_20") (pintype "unspecified"))
    )
    (net (code "45") (name "/C.PC0") (class "Default")
      (node (ref "R32") (pin "2") (pinfunction "2_2") (pintype "input"))
      (node (ref "U.A3") (pin "7") (pinfunction "PC0_7") (pintype "unspecified"))
      (node (ref "U8") (pin "35") (pinfunction "35_35") (pintype "unspecified"))
    )
    (net (code "46") (name "/C.PC3") (class "Default")
      (node (ref "FPC3") (pin "9") (pinfunction "9_9") (pintype "input"))
      (node (ref "U.A3") (pin "10") (pinfunction "PC3_10") (pintype "unspecified"))
      (node (ref "U8") (pin "4") (pinfunction "4_4") (pintype "unspecified"))
    )
    (net (code "47") (name "/C.PC5.FT") (class "Default")
      (node (ref "FPC3") (pin "24") (pinfunction "24_24") (pintype "input"))
      (node (ref "U.A3") (pin "12") (pinfunction "PC5_12") (pintype "unspecified"))
      (node (ref "U8") (pin "30") (pinfunction "30_30") (pintype "unspecified"))
    )
    (net (code "48") (name "/C.PC6.FT") (class "Default")
      (node (ref "FPC3") (pin "23") (pinfunction "23_23") (pintype "input"))
      (node (ref "U.A3") (pin "13") (pinfunction "PC6_13") (pintype "unspecified"))
      (node (ref "U8") (pin "28") (pinfunction "28_28") (pintype "unspecified"))
    )
    (net (code "49") (name "/C.PC7") (class "Default")
      (node (ref "U.A3") (pin "14") (pinfunction "PC7_14") (pintype "unspecified"))
      (node (ref "U8") (pin "33") (pinfunction "33_33") (pintype "unspecified"))
    )
    (net (code "50") (name "/C.PD0") (class "Default")
      (node (ref "U.A3") (pin "5") (pinfunction "PD0_5") (pintype "unspecified"))
      (node (ref "U9") (pin "36") (pinfunction "36_36") (pintype "unspecified"))
    )
    (net (code "51") (name "/C.SWIO") (class "Default")
      (node (ref "FPC1") (pin "6") (pinfunction "6_6") (pintype "unspecified"))
      (node (ref "U.A3") (pin "15") (pinfunction "PD1_15") (pintype "unspecified"))
    )
    (net (code "52") (name "/CC1") (class "Default")
      (node (ref "R5") (pin "2") (pinfunction "2_2") (pintype "input"))
      (node (ref "USB1") (pin "4") (pinfunction "CC1_4") (pintype "unspecified"))
    )
    (net (code "53") (name "/CC2") (class "Default")
      (node (ref "R6") (pin "2") (pinfunction "2_2") (pintype "input"))
      (node (ref "USB1") (pin "10") (pinfunction "CC2_10") (pintype "unspecified"))
    )
    (net (code "54") (name "/D.A0") (class "Default")
      (node (ref "H3") (pin "8") (pinfunction "8_8") (pintype "input"))
      (node (ref "U.A4") (pin "3") (pinfunction "PA2_3") (pintype "unspecified"))
      (node (ref "U8") (pin "37") (pinfunction "37_37") (pintype "unspecified"))
    )
    (net (code "55") (name "/D.A1") (class "Default")
      (node (ref "H3") (pin "6") (pinfunction "6_6") (pintype "input"))
      (node (ref "U.A4") (pin "2") (pinfunction "PA1_2") (pintype "unspecified"))
      (node (ref "U9") (pin "38") (pinfunction "38_38") (pintype "unspecified"))
    )
    (net (code "56") (name "/D.A2") (class "Default")
      (node (ref "U.A4") (pin "11") (pinfunction "PC4_11") (pintype "unspecified"))
      (node (ref "U8") (pin "43") (pinfunction "43_43") (pintype "unspecified"))
    )
    (net (code "57") (name "/D.A3") (class "Default")
      (node (ref "U.A4") (pin "16") (pinfunction "PD2_16") (pintype "unspecified"))
      (node (ref "U9") (pin "6") (pinfunction "6_6") (pintype "unspecified"))
    )
    (net (code "58") (name "/D.A4") (class "Default")
      (node (ref "U.A4") (pin "17") (pinfunction "PD3_17") (pintype "unspecified"))
      (node (ref "U9") (pin "8") (pinfunction "8_8") (pintype "unspecified"))
    )
    (net (code "59") (name "/D.A5") (class "Default")
      (node (ref "U.A4") (pin "19") (pinfunction "PD5_19") (pintype "unspecified"))
      (node (ref "U9") (pin "12") (pinfunction "12_12") (pintype "unspecified"))
    )
    (net (code "60") (name "/D.A6") (class "Default")
      (node (ref "U.A4") (pin "20") (pinfunction "PD6_20") (pintype "unspecified"))
      (node (ref "U9") (pin "14") (pinfunction "14_14") (pintype "unspecified"))
    )
    (net (code "61") (name "/D.A7") (class "Default")
      (node (ref "U.A4") (pin "18") (pinfunction "PD4_18") (pintype "unspecified"))
      (node (ref "U9") (pin "10") (pinfunction "10_10") (pintype "unspecified"))
    )
    (net (code "62") (name "/D.NRST") (class "Default")
      (node (ref "R33") (pin "2") (pinfunction "2_2") (pintype "input"))
      (node (ref "U1") (pin "21") (pinfunction "IO7_21") (pintype "unspecified"))
    )
    (net (code "63") (name "/D.PC0") (class "Default")
      (node (ref "R35") (pin "2") (pinfunction "2_2") (pintype "input"))
      (node (ref "U.A4") (pin "7") (pinfunction "PC0_7") (pintype "unspecified"))
      (node (ref "U8") (pin "41") (pinfunction "41_41") (pintype "unspecified"))
    )
    (net (code "64") (name "/D.PC3") (class "Default")
      (node (ref "U.A4") (pin "10") (pinfunction "PC3_10") (pintype "unspecified"))
      (node (ref "U8") (pin "45") (pinfunction "45_45") (pintype "unspecified"))
    )
    (net (code "65") (name "/D.PC5.FT") (class "Default")
      (node (ref "H3") (pin "10") (pinfunction "10_10") (pintype "input"))
      (node (ref "U.A4") (pin "12") (pinfunction "PC5_12") (pintype "unspecified"))
      (node (ref "U8") (pin "42") (pinfunction "42_42") (pintype "unspecified"))
    )
    (net (code "66") (name "/D.PC6.FT") (class "Default")
      (node (ref "H3") (pin "12") (pinfunction "12_12") (pintype "input"))
      (node (ref "U.A4") (pin "13") (pinfunction "PC6_13") (pintype "unspecified"))
      (node (ref "U8") (pin "40") (pinfunction "40_40") (pintype "unspecified"))
    )
    (net (code "67") (name "/D.PC7") (class "Default")
      (node (ref "U.A4") (pin "14") (pinfunction "PC7_14") (pintype "unspecified"))
      (node (ref "U9") (pin "4") (pinfunction "4_4") (pintype "unspecified"))
    )
    (net (code "68") (name "/D.PD0") (class "Default")
      (node (ref "U.A4") (pin "5") (pinfunction "PD0_5") (pintype "unspecified"))
      (node (ref "U8") (pin "39") (pinfunction "39_39") (pintype "unspecified"))
    )
    (net (code "69") (name "/D.SWIO") (class "Default")
      (node (ref "FPC1") (pin "2") (pinfunction "2_2") (pintype "unspecified"))
      (node (ref "U.A4") (pin "15") (pinfunction "PD1_15") (pintype "unspecified"))
    )
    (net (code "70") (name "/E.A0") (class "Default")
      (node (ref "U.A5") (pin "3") (pinfunction "PA2_3") (pintype "unspecified"))
      (node (ref "U9") (pin "32") (pinfunction "32_32") (pintype "unspecified"))
    )
    (net (code "71") (name "/E.A1") (class "Default")
      (node (ref "U.A5") (pin "2") (pinfunction "PA1_2") (pintype "unspecified"))
      (node (ref "U8") (pin "31") (pinfunction "31_31") (pintype "unspecified"))
    )
    (net (code "72") (name "/E.A2") (class "Default")
      (node (ref "U.A5") (pin "11") (pinfunction "PC4_11") (pintype "unspecified"))
      (node (ref "U9") (pin "35") (pinfunction "35_35") (pintype "unspecified"))
    )
    (net (code "73") (name "/E.A3") (class "Default")
      (node (ref "U.A5") (pin "16") (pinfunction "PD2_16") (pintype "unspecified"))
      (node (ref "U9") (pin "31") (pinfunction "31_31") (pintype "unspecified"))
    )
    (net (code "74") (name "/E.A4") (class "Default")
      (node (ref "U.A5") (pin "17") (pinfunction "PD3_17") (pintype "unspecified"))
      (node (ref "U9") (pin "29") (pinfunction "29_29") (pintype "unspecified"))
    )
    (net (code "75") (name "/E.A5") (class "Default")
      (node (ref "U.A5") (pin "19") (pinfunction "PD5_19") (pintype "unspecified"))
      (node (ref "U9") (pin "25") (pinfunction "25_25") (pintype "unspecified"))
    )
    (net (code "76") (name "/E.A6") (class "Default")
      (node (ref "U.A5") (pin "20") (pinfunction "PD6_20") (pintype "unspecified"))
      (node (ref "U9") (pin "23") (pinfunction "23_23") (pintype "unspecified"))
    )
    (net (code "77") (name "/E.A7") (class "Default")
      (node (ref "U.A5") (pin "18") (pinfunction "PD4_18") (pintype "unspecified"))
      (node (ref "U9") (pin "27") (pinfunction "27_27") (pintype "unspecified"))
    )
    (net (code "78") (name "/E.NRST") (class "Default")
      (node (ref "R36") (pin "2") (pinfunction "2_2") (pintype "input"))
      (node (ref "U1") (pin "19") (pinfunction "IO5_19") (pintype "unspecified"))
    )
    (net (code "79") (name "/E.PC0") (class "Default")
      (node (ref "R38") (pin "2") (pinfunction "2_2") (pintype "input"))
      (node (ref "U.A5") (pin "7") (pinfunction "PC0_7") (pintype "unspecified"))
      (node (ref "U9") (pin "18") (pinfunction "18_18") (pintype "unspecified"))
    )
    (net (code "80") (name "/E.PC3") (class "Default")
      (node (ref "U.A5") (pin "10") (pinfunction "PC3_10") (pintype "unspecified"))
      (node (ref "U9") (pin "37") (pinfunction "37_37") (pintype "unspecified"))
    )
    (net (code "81") (name "/E.PC5.FT") (class "Default")
      (node (ref "U.A5") (pin "12") (pinfunction "PC5_12") (pintype "unspecified"))
      (node (ref "U8") (pin "38") (pinfunction "38_38") (pintype "unspecified"))
    )
    (net (code "82") (name "/E.PC6.FT") (class "Default")
      (node (ref "U.A5") (pin "13") (pinfunction "PC6_13") (pintype "unspecified"))
      (node (ref "U8") (pin "36") (pinfunction "36_36") (pintype "unspecified"))
    )
    (net (code "83") (name "/E.PC7") (class "Default")
      (node (ref "U.A5") (pin "14") (pinfunction "PC7_14") (pintype "unspecified"))
      (node (ref "U9") (pin "33") (pinfunction "33_33") (pintype "unspecified"))
    )
    (net (code "84") (name "/E.PD0") (class "Default")
      (node (ref "U.A5") (pin "5") (pinfunction "PD0_5") (pintype "unspecified"))
      (node (ref "U9") (pin "16") (pinfunction "16_16") (pintype "unspecified"))
    )
    (net (code "85") (name "/E.SWIO") (class "Default")
      (node (ref "FPC1") (pin "3") (pinfunction "3_3") (pintype "unspecified"))
      (node (ref "U.A5") (pin "15") (pinfunction "PD1_15") (pintype "unspecified"))
    )
    (net (code "86") (name "/EN") (class "Default")
      (node (ref "C1") (pin "1") (pinfunction "1_1") (pintype "input"))
      (node (ref "C20") (pin "1") (pinfunction "1_1") (pintype "input"))
      (node (ref "H3") (pin "9") (pinfunction "9_9") (pintype "input"))
      (node (ref "R4") (pin "1") (pinfunction "1_1") (pintype "input"))
      (node (ref "SW1") (pin "1") (pinfunction "1_1") (pintype "input"))
      (node (ref "SW1") (pin "2") (pinfunction "2_2") (pintype "input"))
      (node (ref "U1") (pin "8") (pinfunction "EN_8") (pintype "unspecified"))
      (node (ref "U9") (pin "47") (pinfunction "47_47") (pintype "unspecified"))
    )
    (net (code "87") (name "/GPIO9{slash}BOOT") (class "Default")
      (node (ref "R17") (pin "1") (pinfunction "1_1") (pintype "input"))
      (node (ref "SW2") (pin "3") (pinfunction "3_3") (pintype "input"))
      (node (ref "SW2") (pin "4") (pinfunction "4_4") (pintype "input"))
      (node (ref "U1") (pin "23") (pinfunction "IO9_23") (pintype "unspecified"))
      (node (ref "U9") (pin "49") (pinfunction "49_49") (pintype "unspecified"))
    )
    (net (code "88") (name "/IO0") (class "Default")
      (node (ref "H3") (pin "1") (pinfunction "1_1") (pintype "input"))
      (node (ref "U1") (pin "12") (pinfunction "IO0_12") (pintype "unspecified"))
      (node (ref "U9") (pin "45") (pinfunction "45_45") (pintype "unspecified"))
    )
    (net (code "89") (name "/IO2") (class "Default")
      (node (ref "R18") (pin "1") (pinfunction "1_1") (pintype "input"))
      (node (ref "U1") (pin "5") (pinfunction "IO2_5") (pintype "unspecified"))
      (node (ref "U9") (pin "43") (pinfunction "43_43") (pintype "unspecified"))
    )
    (net (code "90") (name "/IO3") (class "Default")
      (node (ref "H3") (pin "3") (pinfunction "3_3") (pintype "input"))
      (node (ref "U1") (pin "6") (pinfunction "IO3_6") (pintype "unspecified"))
      (node (ref "U9") (pin "41") (pinfunction "41_41") (pintype "unspecified"))
    )
    (net (code "91") (name "/RXD0") (class "Default")
      (node (ref "FPC2") (pin "3") (pinfunction "3_3") (pintype "input"))
      (node (ref "H3") (pin "14") (pinfunction "14_14") (pintype "input"))
      (node (ref "U1") (pin "30") (pinfunction "RXD0_30") (pintype "unspecified"))
      (node (ref "U9") (pin "50") (pinfunction "50_50") (pintype "unspecified"))
    )
    (net (code "92") (name "/SCL") (class "Default")
      (node (ref "FPC2") (pin "4") (pinfunction "4_4") (pintype "input"))
      (node (ref "H3") (pin "7") (pinfunction "7_7") (pintype "input"))
      (node (ref "R20") (pin "1") (pinfunction "1_1") (pintype "input"))
      (node (ref "U.A1") (pin "9") (pinfunction "PC2_9") (pintype "unspecified"))
      (node (ref "U.A2") (pin "9") (pinfunction "PC2_9") (pintype "unspecified"))
      (node (ref "U.A3") (pin "9") (pinfunction "PC2_9") (pintype "unspecified"))
      (node (ref "U.A4") (pin "9") (pinfunction "PC2_9") (pintype "unspecified"))
      (node (ref "U.A5") (pin "9") (pinfunction "PC2_9") (pintype "unspecified"))
      (node (ref "U1") (pin "22") (pinfunction "IO8_22") (pintype "unspecified"))
      (node (ref "U9") (pin "44") (pinfunction "44_44") (pintype "unspecified"))
    )
    (net (code "93") (name "/SDA") (class "Default")
      (node (ref "FPC2") (pin "5") (pinfunction "5_5") (pintype "input"))
      (node (ref "H3") (pin "5") (pinfunction "5_5") (pintype "input"))
      (node (ref "R19") (pin "1") (pinfunction "1_1") (pintype "input"))
      (node (ref "U.A1") (pin "8") (pinfunction "PC1_8") (pintype "unspecified"))
      (node (ref "U.A2") (pin "8") (pinfunction "PC1_8") (pintype "unspecified"))
      (node (ref "U.A3") (pin "8") (pinfunction "PC1_8") (pintype "unspecified"))
      (node (ref "U.A4") (pin "8") (pinfunction "PC1_8") (pintype "unspecified"))
      (node (ref "U.A5") (pin "8") (pinfunction "PC1_8") (pintype "unspecified"))
      (node (ref "U1") (pin "16") (pinfunction "IO10_16") (pintype "unspecified"))
      (node (ref "U9") (pin "42") (pinfunction "42_42") (pintype "unspecified"))
    )
    (net (code "94") (name "/TXD0") (class "Default")
      (node (ref "FPC2") (pin "2") (pinfunction "2_2") (pintype "input"))
      (node (ref "H3") (pin "16") (pinfunction "16_16") (pintype "input"))
      (node (ref "U1") (pin "31") (pinfunction "TXD0_31") (pintype "unspecified"))
      (node (ref "U9") (pin "48") (pinfunction "48_48") (pintype "unspecified"))
    )
    (net (code "95") (name "/USB_D+") (class "Default")
      (node (ref "R8") (pin "1") (pinfunction "1_1") (pintype "input"))
      (node (ref "U1") (pin "27") (pinfunction "IO19_27") (pintype "unspecified"))
    )
    (net (code "96") (name "/USB_D-") (class "Default")
      (node (ref "R7") (pin "1") (pinfunction "1_1") (pintype "input"))
      (node (ref "U1") (pin "26") (pinfunction "IO18_26") (pintype "unspecified"))
    )
    (net (code "97") (name "/VBUS_USB") (class "Default")
      (node (ref "D3") (pin "2") (pinfunction "A_2") (pintype "unspecified"))
      (node (ref "U2") (pin "2") (pinfunction "2_2") (pintype "unspecified"))
      (node (ref "USB1") (pin "11") (pinfunction "VBUS_11") (pintype "unspecified"))
      (node (ref "USB1") (pin "2") (pinfunction "VBUS_2") (pintype "unspecified"))
    )
    (net (code "98") (name "GND") (class "Default")
      (node (ref "C1") (pin "2") (pinfunction "2_2") (pintype "input"))
      (node (ref "C2") (pin "2") (pinfunction "2_2") (pintype "input"))
      (node (ref "C20") (pin "2") (pinfunction "2_2") (pintype "input"))
      (node (ref "C22") (pin "2") (pinfunction "2_2") (pintype "input"))
      (node (ref "C23") (pin "2") (pinfunction "2_2") (pintype "input"))
      (node (ref "C24") (pin "2") (pinfunction "2_2") (pintype "input"))
      (node (ref "C25") (pin "2") (pinfunction "2_2") (pintype "input"))
      (node (ref "C26") (pin "2") (pinfunction "2_2") (pintype "input"))
      (node (ref "C27") (pin "2") (pinfunction "2_2") (pintype "input"))
      (node (ref "C28") (pin "2") (pinfunction "2_2") (pintype "input"))
      (node (ref "C29") (pin "2") (pinfunction "2_2") (pintype "input"))
      (node (ref "C3") (pin "2") (pinfunction "2_2") (pintype "input"))
      (node (ref "C30") (pin "2") (pinfunction "2_2") (pintype "input"))
      (node (ref "C31") (pin "2") (pinfunction "2_2") (pintype "input"))
      (node (ref "C4") (pin "2") (pinfunction "2_2") (pintype "input"))
      (node (ref "C5") (pin "2") (pinfunction "2_2") (pintype "input"))
      (node (ref "D1") (pin "1") (pinfunction "1_1") (pintype "unspecified"))
      (node (ref "D4") (pin "1") (pinfunction "1_1") (pintype "unspecified"))
      (node (ref "FPC1") (pin "10") (pinfunction "10_10") (pintype "unspecified"))
      (node (ref "FPC1") (pin "8") (pinfunction "8_8") (pintype "unspecified"))
      (node (ref "FPC1") (pin "9") (pinfunction "9_9") (pintype "unspecified"))
      (node (ref "FPC2") (pin "1") (pinfunction "1_1") (pintype "input"))
      (node (ref "FPC2") (pin "7") (pinfunction "7_7") (pintype "input"))
      (node (ref "FPC2") (pin "8") (pinfunction "8_8") (pintype "input"))
      (node (ref "FPC3") (pin "1") (pinfunction "1_1") (pintype "input"))
      (node (ref "FPC3") (pin "2") (pinfunction "2_2") (pintype "input"))
      (node (ref "FPC3") (pin "39") (pinfunction "39_39") (pintype "input"))
      (node (ref "FPC3") (pin "40") (pinfunction "40_40") (pintype "input"))
      (node (ref "FPC3") (pin "41") (pinfunction "41_41") (pintype "input"))
      (node (ref "FPC3") (pin "42") (pinfunction "42_42") (pintype "input"))
      (node (ref "H3") (pin "13") (pinfunction "13_13") (pintype "input"))
      (node (ref "H3") (pin "15") (pinfunction "15_15") (pintype "input"))
      (node (ref "LED2") (pin "2") (pinfunction "A_2") (pintype "unspecified"))
      (node (ref "LED3") (pin "2") (pinfunction "A_2") (pintype "unspecified"))
      (node (ref "LED4") (pin "2") (pinfunction "A_2") (pintype "unspecified"))
      (node (ref "LED5") (pin "2") (pinfunction "A_2") (pintype "unspecified"))
      (node (ref "LED6") (pin "2") (pinfunction "A_2") (pintype "unspecified"))
      (node (ref "R44") (pin "1") (pinfunction "1_1") (pintype "input"))
      (node (ref "R45") (pin "1") (pinfunction "1_1") (pintype "input"))
      (node (ref "R5") (pin "1") (pinfunction "1_1") (pintype "input"))
      (node (ref "R6") (pin "1") (pinfunction "1_1") (pintype "input"))
      (node (ref "SW1") (pin "3") (pinfunction "3_3") (pintype "input"))
      (node (ref "SW1") (pin "4") (pinfunction "4_4") (pintype "input"))
      (node (ref "SW2") (pin "1") (pinfunction "1_1") (pintype "input"))
      (node (ref "SW2") (pin "2") (pinfunction "2_2") (pintype "input"))
      (node (ref "U.A1") (pin "21") (pinfunction "VSS_21") (pintype "unspecified"))
      (node (ref "U.A1") (pin "4") (pinfunction "VSS_4") (pintype "unspecified"))
      (node (ref "U.A2") (pin "21") (pinfunction "VSS_21") (pintype "unspecified"))
      (node (ref "U.A2") (pin "4") (pinfunction "VSS_4") (pintype "unspecified"))
      (node (ref "U.A3") (pin "21") (pinfunction "VSS_21") (pintype "unspecified"))
      (node (ref "U.A3") (pin "4") (pinfunction "VSS_4") (pintype "unspecified"))
      (node (ref "U.A4") (pin "21") (pinfunction "VSS_21") (pintype "unspecified"))
      (node (ref "U.A4") (pin "4") (pinfunction "VSS_4") (pintype "unspecified"))
      (node (ref "U.A5") (pin "21") (pinfunction "VSS_21") (pintype "unspecified"))
      (node (ref "U.A5") (pin "4") (pinfunction "VSS_4") (pintype "unspecified"))
      (node (ref "U1") (pin "1") (pinfunction "GND_1") (pintype "unspecified"))
      (node (ref "U1") (pin "11") (pinfunction "GND_11") (pintype "unspecified"))
      (node (ref "U1") (pin "14") (pinfunction "GND_14") (pintype "unspecified"))
      (node (ref "U1") (pin "2") (pinfunction "GND_2") (pintype "unspecified"))
      (node (ref "U1") (pin "36") (pinfunction "GND_36") (pintype "unspecified"))
      (node (ref "U1") (pin "37") (pinfunction "GND_37") (pintype "unspecified"))
      (node (ref "U1") (pin "38") (pinfunction "GND_38") (pintype "unspecified"))
      (node (ref "U1") (pin "39") (pinfunction "GND_39") (pintype "unspecified"))
      (node (ref "U1") (pin "40") (pinfunction "GND_40") (pintype "unspecified"))
      (node (ref "U1") (pin "41") (pinfunction "GND_41") (pintype "unspecified"))
      (node (ref "U1") (pin "42") (pinfunction "GND_42") (pintype "unspecified"))
      (node (ref "U1") (pin "43") (pinfunction "GND_43") (pintype "unspecified"))
      (node (ref "U1") (pin "44") (pinfunction "GND_44") (pintype "unspecified"))
      (node (ref "U1") (pin "45") (pinfunction "GND_45") (pintype "unspecified"))
      (node (ref "U1") (pin "46") (pinfunction "GND_46") (pintype "unspecified"))
      (node (ref "U1") (pin "47") (pinfunction "GND_47") (pintype "unspecified"))
      (node (ref "U1") (pin "48") (pinfunction "GND_48") (pintype "unspecified"))
      (node (ref "U1") (pin "49") (pinfunction "GND_49") (pintype "unspecified"))
      (node (ref "U1") (pin "50") (pinfunction "GND_50") (pintype "unspecified"))
      (node (ref "U1") (pin "51") (pinfunction "GND_51") (pintype "unspecified"))
      (node (ref "U1") (pin "52") (pinfunction "GND_52") (pintype "unspecified"))
      (node (ref "U1") (pin "53") (pinfunction "GND_53") (pintype "unspecified"))
      (node (ref "U13") (pin "2") (pinfunction "GND_2") (pintype "unspecified"))
      (node (ref "U2") (pin "1") (pinfunction "1_1") (pintype "unspecified"))
      (node (ref "U3") (pin "1") (pinfunction "1_1") (pintype "unspecified"))
      (node (ref "U4") (pin "1") (pinfunction "1_1") (pintype "unspecified"))
      (node (ref "U8") (pin "19") (pinfunction "19_19") (pintype "unspecified"))
      (node (ref "U8") (pin "20") (pinfunction "20_20") (pintype "unspecified"))
      (node (ref "U8") (pin "21") (pinfunction "21_21") (pintype "unspecified"))
      (node (ref "U8") (pin "22") (pinfunction "22_22") (pintype "unspecified"))
      (node (ref "U9") (pin "19") (pinfunction "19_19") (pintype "unspecified"))
      (node (ref "U9") (pin "20") (pinfunction "20_20") (pintype "unspecified"))
      (node (ref "U9") (pin "21") (pinfunction "21_21") (pintype "unspecified"))
      (node (ref "U9") (pin "22") (pinfunction "22_22") (pintype "unspecified"))
      (node (ref "U9") (pin "46") (pinfunction "46_46") (pintype "unspecified"))
      (node (ref "USB1") (pin "1") (pinfunction "GND_1") (pintype "unspecified"))
      (node (ref "USB1") (pin "12") (pinfunction "GND_12") (pintype "unspecified"))
      (node (ref "USB1") (pin "13") (pinfunction "SHELL_13") (pintype "unspecified"))
      (node (ref "USB1") (pin "14") (pinfunction "SHELL_14") (pintype "unspecified"))
    )
    (net (code "99") (name "Net-(LED2-K)") (class "Default")
      (node (ref "LED2") (pin "1") (pinfunction "K_1") (pintype "unspecified"))
      (node (ref "R26") (pin "1") (pinfunction "1_1") (pintype "input"))
    )
    (net (code "100") (name "Net-(LED3-K)") (class "Default")
      (node (ref "LED3") (pin "1") (pinfunction "K_1") (pintype "unspecified"))
      (node (ref "R29") (pin "1") (pinfunction "1_1") (pintype "input"))
    )
    (net (code "101") (name "Net-(LED4-K)") (class "Default")
      (node (ref "LED4") (pin "1") (pinfunction "K_1") (pintype "unspecified"))
      (node (ref "R32") (pin "1") (pinfunction "1_1") (pintype "input"))
    )
    (net (code "102") (name "Net-(LED5-K)") (class "Default")
      (node (ref "LED5") (pin "1") (pinfunction "K_1") (pintype "unspecified"))
      (node (ref "R35") (pin "1") (pinfunction "1_1") (pintype "input"))
    )
    (net (code "103") (name "Net-(LED6-K)") (class "Default")
      (node (ref "LED6") (pin "1") (pinfunction "K_1") (pintype "unspecified"))
      (node (ref "R38") (pin "1") (pinfunction "1_1") (pintype "input"))
    )
    (net (code "104") (name "Net-(Q14-G)") (class "Default")
      (node (ref "Q14") (pin "1") (pinfunction "G_1") (pintype "unspecified"))
      (node (ref "R44") (pin "2") (pinfunction "2_2") (pintype "input"))
      (node (ref "U14") (pin "3") (pinfunction "BIAS_3") (pintype "unspecified"))
    )
    (net (code "105") (name "Net-(U.A1-PD7)") (class "Default")
      (node (ref "R24") (pin "1") (pinfunction "1_1") (pintype "input"))
      (node (ref "R25") (pin "1") (pinfunction "1_1") (pintype "input"))
      (node (ref "U.A1") (pin "1") (pinfunction "PD7_1") (pintype "unspecified"))
    )
    (net (code "106") (name "Net-(U.A2-PD7)") (class "Default")
      (node (ref "R27") (pin "1") (pinfunction "1_1") (pintype "input"))
      (node (ref "R28") (pin "1") (pinfunction "1_1") (pintype "input"))
      (node (ref "U.A2") (pin "1") (pinfunction "PD7_1") (pintype "unspecified"))
    )
    (net (code "107") (name "Net-(U.A3-PD7)") (class "Default")
      (node (ref "R30") (pin "1") (pinfunction "1_1") (pintype "input"))
      (node (ref "R31") (pin "1") (pinfunction "1_1") (pintype "input"))
      (node (ref "U.A3") (pin "1") (pinfunction "PD7_1") (pintype "unspecified"))
    )
    (net (code "108") (name "Net-(U.A4-PD7)") (class "Default")
      (node (ref "R33") (pin "1") (pinfunction "1_1") (pintype "input"))
      (node (ref "R34") (pin "1") (pinfunction "1_1") (pintype "input"))
      (node (ref "U.A4") (pin "1") (pinfunction "PD7_1") (pintype "unspecified"))
    )
    (net (code "109") (name "Net-(U.A5-PD7)") (class "Default")
      (node (ref "R36") (pin "1") (pinfunction "1_1") (pintype "input"))
      (node (ref "R37") (pin "1") (pinfunction "1_1") (pintype "input"))
      (node (ref "U.A5") (pin "1") (pinfunction "PD7_1") (pintype "unspecified"))
    )
    (net (code "110") (name "Net-(U14-REF)") (class "Default")
      (node (ref "R45") (pin "2") (pinfunction "2_2") (pintype "input"))
      (node (ref "U14") (pin "2") (pinfunction "REF_2") (pintype "unspecified"))
    )
    (net (code "111") (name "Net-(USB1-DN1)") (class "Default")
      (node (ref "R7") (pin "2") (pinfunction "2_2") (pintype "input"))
      (node (ref "U4") (pin "2") (pinfunction "2_2") (pintype "unspecified"))
      (node (ref "USB1") (pin "5") (pinfunction "DN2_5") (pintype "unspecified"))
      (node (ref "USB1") (pin "7") (pinfunction "DN1_7") (pintype "unspecified"))
    )
    (net (code "112") (name "Net-(USB1-DP1)") (class "Default")
      (node (ref "R8") (pin "2") (pinfunction "2_2") (pintype "input"))
      (node (ref "U3") (pin "2") (pinfunction "2_2") (pintype "unspecified"))
      (node (ref "USB1") (pin "6") (pinfunction "DP1_6") (pintype "unspecified"))
      (node (ref "USB1") (pin "8") (pinfunction "DP2_8") (pintype "unspecified"))
    )
    (net (code "113") (name "unconnected-(FPC1-Pad7)") (class "Default")
      (node (ref "FPC1") (pin "7") (pinfunction "7_7") (pintype "unspecified"))
    )
    (net (code "114") (name "unconnected-(SW1-Pad5)") (class "Default")
      (node (ref "SW1") (pin "5") (pinfunction "5_5") (pintype "input+no_connect"))
    )
    (net (code "115") (name "unconnected-(SW1-Pad6)") (class "Default")
      (node (ref "SW1") (pin "6") (pinfunction "6_6") (pintype "input+no_connect"))
    )
    (net (code "116") (name "unconnected-(SW2-Pad5)") (class "Default")
      (node (ref "SW2") (pin "5") (pinfunction "5_5") (pintype "input+no_connect"))
    )
    (net (code "117") (name "unconnected-(SW2-Pad6)") (class "Default")
      (node (ref "SW2") (pin "6") (pinfunction "6_6") (pintype "input+no_connect"))
    )
    (net (code "118") (name "unconnected-(U1-NC-Pad4)") (class "Default")
      (node (ref "U1") (pin "4") (pinfunction "NC_4") (pintype "unspecified+no_connect"))
    )
    (net (code "119") (name "unconnected-(U1-NC-Pad7)") (class "Default")
      (node (ref "U1") (pin "7") (pinfunction "NC_7") (pintype "unspecified+no_connect"))
    )
    (net (code "120") (name "unconnected-(U1-NC-Pad9)") (class "Default")
      (node (ref "U1") (pin "9") (pinfunction "NC_9") (pintype "unspecified+no_connect"))
    )
    (net (code "121") (name "unconnected-(U1-NC-Pad10)") (class "Default")
      (node (ref "U1") (pin "10") (pinfunction "NC_10") (pintype "unspecified+no_connect"))
    )
    (net (code "122") (name "unconnected-(U1-NC-Pad15)") (class "Default")
      (node (ref "U1") (pin "15") (pinfunction "NC_15") (pintype "unspecified+no_connect"))
    )
    (net (code "123") (name "unconnected-(U1-NC-Pad17)") (class "Default")
      (node (ref "U1") (pin "17") (pinfunction "NC_17") (pintype "unspecified+no_connect"))
    )
    (net (code "124") (name "unconnected-(U1-NC-Pad24)") (class "Default")
      (node (ref "U1") (pin "24") (pinfunction "NC_24") (pintype "unspecified+no_connect"))
    )
    (net (code "125") (name "unconnected-(U1-NC-Pad25)") (class "Default")
      (node (ref "U1") (pin "25") (pinfunction "NC_25") (pintype "unspecified+no_connect"))
    )
    (net (code "126") (name "unconnected-(U1-NC-Pad28)") (class "Default")
      (node (ref "U1") (pin "28") (pinfunction "NC_28") (pintype "unspecified+no_connect"))
    )
    (net (code "127") (name "unconnected-(U1-NC-Pad29)") (class "Default")
      (node (ref "U1") (pin "29") (pinfunction "NC_29") (pintype "unspecified+no_connect"))
    )
    (net (code "128") (name "unconnected-(U1-NC-Pad32)") (class "Default")
      (node (ref "U1") (pin "32") (pinfunction "NC_32") (pintype "unspecified+no_connect"))
    )
    (net (code "129") (name "unconnected-(U1-NC-Pad33)") (class "Default")
      (node (ref "U1") (pin "33") (pinfunction "NC_33") (pintype "unspecified+no_connect"))
    )
    (net (code "130") (name "unconnected-(U1-NC-Pad34)") (class "Default")
      (node (ref "U1") (pin "34") (pinfunction "NC_34") (pintype "unspecified+no_connect"))
    )
    (net (code "131") (name "unconnected-(U1-NC-Pad35)") (class "Default")
      (node (ref "U1") (pin "35") (pinfunction "NC_35") (pintype "unspecified+no_connect"))
    )
    (net (code "132") (name "unconnected-(U13-NC-Pad4)") (class "Default")
      (node (ref "U13") (pin "4") (pinfunction "NC_4") (pintype "unspecified+no_connect"))
    )
    (net (code "133") (name "unconnected-(U14-NC-Pad1)") (class "Default")
      (node (ref "U14") (pin "1") (pinfunction "NC_1") (pintype "unspecified+no_connect"))
    )
    (net (code "134") (name "unconnected-(U14-NC-Pad5)") (class "Default")
      (node (ref "U14") (pin "5") (pinfunction "NC_5") (pintype "unspecified+no_connect"))
    )
    (net (code "135") (name "unconnected-(USB1-SBU1-Pad9)") (class "Default")
      (node (ref "USB1") (pin "9") (pinfunction "SBU1_9") (pintype "unspecified+no_connect"))
    )
    (net (code "136") (name "unconnected-(USB1-SBU2-Pad3)") (class "Default")
      (node (ref "USB1") (pin "3") (pinfunction "SBU2_3") (pintype "unspecified+no_connect"))
    )
  )
)
